# pic18f13k50_2.net
KiCad netlist of a schematic drawn in EAGLE
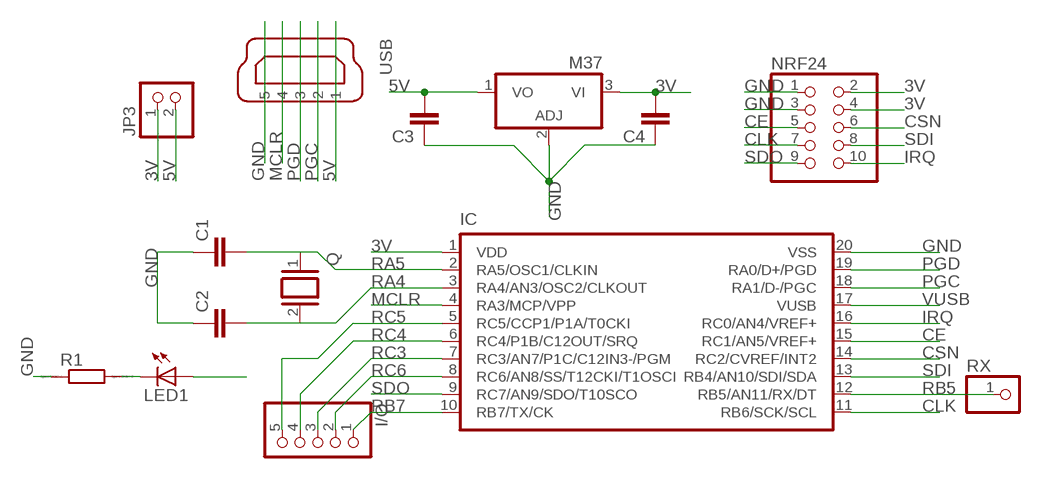
[diagram p0: schematic, sheet 1]

(export (version "E")
  (design (tool "Eeschema 10.0.6"))
  (components
    (comp (ref "C1")
      (value "C-EUC0805")
      (footprint "eagle-import:C0805")
      (libsource (lib "eagle-import") (part "C-EUC0805"))
    )
    (comp (ref "C2")
      (value "C-EUC0805")
      (footprint "eagle-import:C0805")
      (libsource (lib "eagle-import") (part "C-EUC0805"))
    )
    (comp (ref "C3")
      (value "C-EU025-025X050")
      (footprint "eagle-import:C025-025X050")
      (libsource (lib "eagle-import") (part "C-EU025-025X050"))
    )
    (comp (ref "C4")
      (value "C-EU025-025X050")
      (footprint "eagle-import:C025-025X050")
      (libsource (lib "eagle-import") (part "C-EU025-025X050"))
    )
    (comp (ref "I/O")
      (value "PINHD-1X5")
      (footprint "eagle-import:1X05")
      (libsource (lib "eagle-import") (part "PINHD-1X5"))
    )
    (comp (ref "IC")
      (value "PIC18F13K50")
      (footprint "eagle-import:SSOP20")
      (libsource (lib "eagle-import") (part "PIC18F13K50"))
    )
    (comp (ref "JP3")
      (value "PINHD-1X2")
      (footprint "eagle-import:1X02")
      (libsource (lib "eagle-import") (part "PINHD-1X2"))
    )
    (comp (ref "LED1")
      (value "LEDCHIP-LED0805")
      (footprint "eagle-import:CHIP-LED0805")
      (libsource (lib "eagle-import") (part "LEDCHIP-LED0805"))
    )
    (comp (ref "M37")
      (value "337IMP")
      (footprint "eagle-import:SOT223")
      (libsource (lib "eagle-import") (part "337IMP"))
    )
    (comp (ref "NRF24")
      (value "PINHD-2X5")
      (footprint "eagle-import:2X05")
      (libsource (lib "eagle-import") (part "PINHD-2X5"))
    )
    (comp (ref "Q")
      (value "XTAL/S")
      (footprint "eagle-import:QS")
      (libsource (lib "eagle-import") (part "XTAL/S"))
    )
    (comp (ref "R1") (value "R") (footprint "eagle-import:R0805") (libsource (lib "eagle-import") (part "R")))
    (comp (ref "RX")
      (value "PINHD-1X1")
      (footprint "eagle-import:1X01")
      (libsource (lib "eagle-import") (part "PINHD-1X1"))
    )
    (comp (ref "USB")
      (value "MINI-USB-32005-201")
      (footprint "eagle-import:32005-201")
      (libsource (lib "eagle-import") (part "MINI-USB-32005-201"))
    )
  )
  (nets
    (net (code "1") (name "/3V") (class "Default")
      (node (ref "C4") (pin "2") (pinfunction "2_2") (pintype "passive"))
      (node (ref "IC") (pin "1") (pinfunction "VDD_1") (pintype "power_in"))
      (node (ref "JP3") (pin "1") (pinfunction "1_1") (pintype "passive"))
      (node (ref "M37") (pin "3") (pinfunction "VI_3") (pintype "input"))
      (node (ref "NRF24") (pin "2") (pinfunction "2_2") (pintype "passive"))
      (node (ref "NRF24") (pin "4") (pinfunction "4_4") (pintype "passive"))
    )
    (net (code "2") (name "/5V") (class "Default")
      (node (ref "C3") (pin "2") (pinfunction "2_2") (pintype "passive"))
      (node (ref "JP3") (pin "2") (pinfunction "2_2") (pintype "passive"))
      (node (ref "M37") (pin "1") (pinfunction "VO_1") (pintype "passive"))
      (node (ref "USB") (pin "1") (pinfunction "1_1") (pintype "passive"))
    )
    (net (code "3") (name "/CE") (class "Default")
      (node (ref "IC") (pin "15") (pinfunction "RC1/AN5/VREF+_15") (pintype "bidirectional"))
      (node (ref "NRF24") (pin "5") (pinfunction "5_5") (pintype "passive"))
    )
    (net (code "4") (name "/CLK") (class "Default")
      (node (ref "IC") (pin "11") (pinfunction "RB6/SCK/SCL_11") (pintype "bidirectional"))
      (node (ref "NRF24") (pin "7") (pinfunction "7_7") (pintype "passive"))
    )
    (net (code "5") (name "/CSN") (class "Default")
      (node (ref "IC") (pin "14") (pinfunction "RC2/CVREF/INT2_14") (pintype "bidirectional"))
      (node (ref "NRF24") (pin "6") (pinfunction "6_6") (pintype "passive"))
    )
    (net (code "6") (name "/GND") (class "Default")
      (node (ref "C1") (pin "1") (pinfunction "1_1") (pintype "passive"))
      (node (ref "C2") (pin "1") (pinfunction "1_1") (pintype "passive"))
      (node (ref "C3") (pin "1") (pinfunction "1_1") (pintype "passive"))
      (node (ref "C4") (pin "1") (pinfunction "1_1") (pintype "passive"))
      (node (ref "IC") (pin "20") (pinfunction "VSS_20") (pintype "power_in"))
      (node (ref "M37") (pin "2") (pinfunction "ADJ_2") (pintype "input"))
      (node (ref "NRF24") (pin "1") (pinfunction "1_1") (pintype "passive"))
      (node (ref "NRF24") (pin "3") (pinfunction "3_3") (pintype "passive"))
      (node (ref "R1") (pin "1") (pinfunction "1_1") (pintype "passive"))
      (node (ref "USB") (pin "5") (pinfunction "5_5") (pintype "passive"))
    )
    (net (code "7") (name "/IRQ") (class "Default")
      (node (ref "IC") (pin "16") (pinfunction "RC0/AN4/VREF+_16") (pintype "bidirectional"))
      (node (ref "NRF24") (pin "10") (pinfunction "10_10") (pintype "passive"))
    )
    (net (code "8") (name "/MCLR") (class "Default")
      (node (ref "IC") (pin "4") (pinfunction "RA3/MCP/VPP_4") (pintype "bidirectional"))
      (node (ref "USB") (pin "4") (pinfunction "4_4") (pintype "passive"))
    )
    (net (code "9") (name "/PGC") (class "Default")
      (node (ref "IC") (pin "18") (pinfunction "RA1/D-/PGC_18") (pintype "bidirectional"))
      (node (ref "USB") (pin "2") (pinfunction "2_2") (pintype "passive"))
    )
    (net (code "10") (name "/PGD") (class "Default")
      (node (ref "IC") (pin "19") (pinfunction "RA0/D+/PGD_19") (pintype "bidirectional"))
      (node (ref "USB") (pin "3") (pinfunction "3_3") (pintype "passive"))
    )
    (net (code "11") (name "/RA4") (class "Default")
      (node (ref "C2") (pin "2") (pinfunction "2_2") (pintype "passive"))
      (node (ref "IC") (pin "3") (pinfunction "RA4/AN3/OSC2/CLKOUT_3") (pintype "input"))
      (node (ref "Q") (pin "2") (pinfunction "2_2") (pintype "passive"))
    )
    (net (code "12") (name "/RA5") (class "Default")
      (node (ref "C1") (pin "2") (pinfunction "2_2") (pintype "passive"))
      (node (ref "IC") (pin "2") (pinfunction "RA5/OSC1/CLKIN_2") (pintype "power_in"))
      (node (ref "Q") (pin "1") (pinfunction "1_1") (pintype "passive"))
    )
    (net (code "13") (name "/RB5") (class "Default")
      (node (ref "IC") (pin "12") (pinfunction "RB5/AN11/RX/DT_12") (pintype "bidirectional"))
      (node (ref "RX") (pin "1") (pinfunction "1_1") (pintype "passive"))
    )
    (net (code "14") (name "/RB7") (class "Default")
      (node (ref "I/O") (pin "1") (pinfunction "1_1") (pintype "passive"))
      (node (ref "IC") (pin "10") (pinfunction "RB7/TX/CK_10") (pintype "power_in"))
      (node (ref "LED1") (pin "A") (pinfunction "A_A") (pintype "passive"))
    )
    (net (code "15") (name "/RC3") (class "Default")
      (node (ref "I/O") (pin "3") (pinfunction "3_3") (pintype "passive"))
      (node (ref "IC") (pin "7") (pinfunction "RC3/AN7/P1C/C12IN3-/PGM_7") (pintype "bidirectional"))
    )
    (net (code "16") (name "/RC4") (class "Default")
      (node (ref "I/O") (pin "4") (pinfunction "4_4") (pintype "passive"))
      (node (ref "IC") (pin "6") (pinfunction "RC4/P1B/C12OUT/SRQ_6") (pintype "bidirectional"))
    )
    (net (code "17") (name "/RC5") (class "Default")
      (node (ref "I/O") (pin "5") (pinfunction "5_5") (pintype "passive"))
      (node (ref "IC") (pin "5") (pinfunction "RC5/CCP1/P1A/T0CKI_5") (pintype "bidirectional"))
    )
    (net (code "18") (name "/RC6") (class "Default")
      (node (ref "I/O") (pin "2") (pinfunction "2_2") (pintype "passive"))
      (node (ref "IC") (pin "8") (pinfunction "RC6/AN8/SS/T12CKI/T1OSCI_8") (pintype "bidirectional"))
    )
    (net (code "19") (name "/SDI") (class "Default")
      (node (ref "IC") (pin "13") (pinfunction "RB4/AN10/SDI/SDA_13") (pintype "bidirectional"))
      (node (ref "NRF24") (pin "8") (pinfunction "8_8") (pintype "passive"))
    )
    (net (code "20") (name "/SDO") (class "Default")
      (node (ref "IC") (pin "9") (pinfunction "RC7/AN9/SDO/T10SCO_9") (pintype "bidirectional"))
      (node (ref "NRF24") (pin "9") (pinfunction "9_9") (pintype "passive"))
    )
    (net (code "21") (name "/VUSB") (class "Default")
      (node (ref "IC") (pin "17") (pinfunction "VUSB_17") (pintype "bidirectional"))
    )
    (net (code "22") (name "Net-(LED1-PadC)") (class "Default")
      (node (ref "LED1") (pin "C") (pinfunction "C_C") (pintype "passive"))
      (node (ref "R1") (pin "2") (pinfunction "2_2") (pintype "passive"))
    )
  )
)
